# working.net
KiCad netlist of a schematic drawn in EAGLE
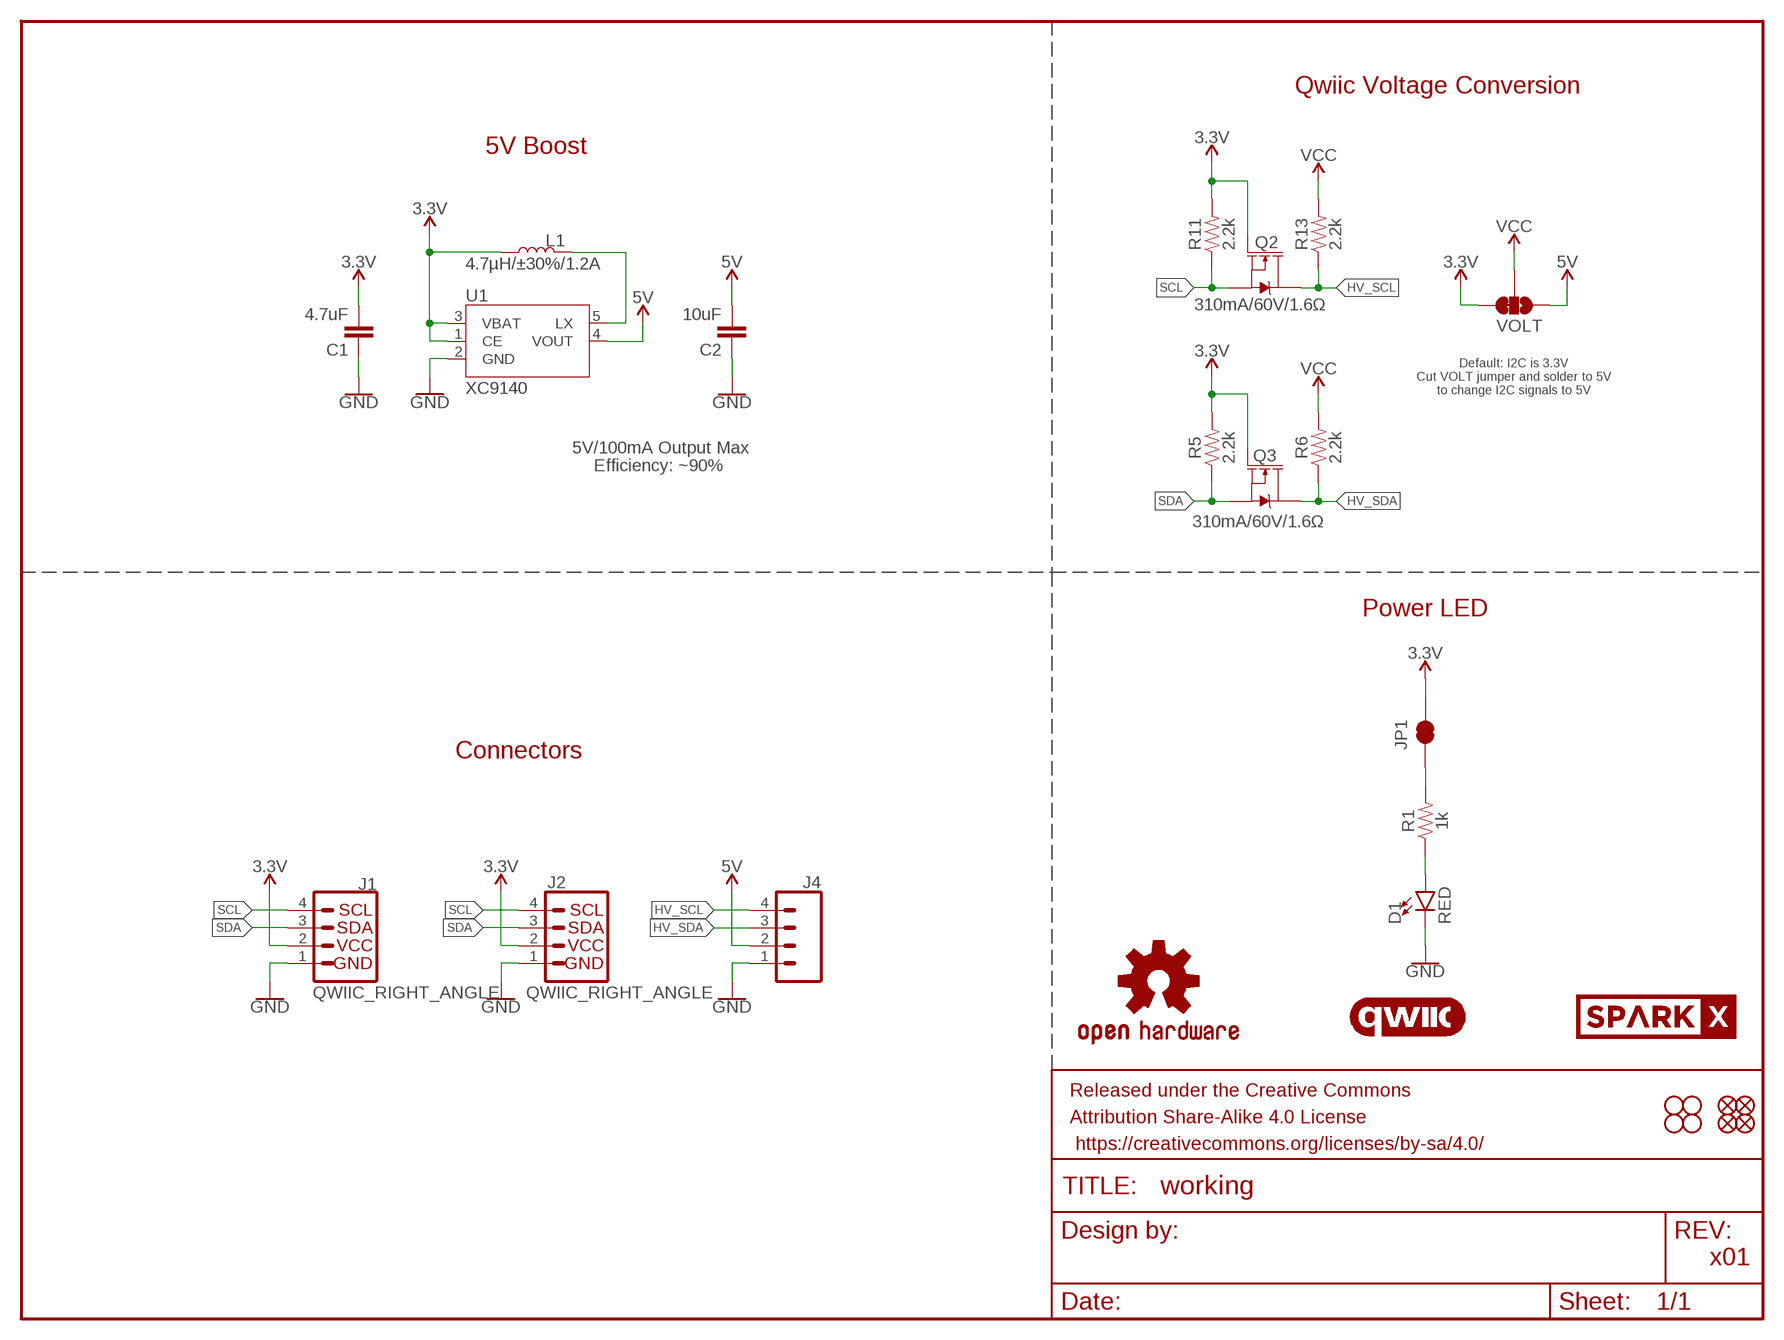
[diagram p0: schematic, sheet 1]

(export (version "E")
  (design (tool "Eeschema 10.0.6"))
  (components
    (comp (ref "C1")
      (value "4.7uF")
      (footprint "eagle-import:0603")
      (libsource (lib "eagle-import") (part "4.7UF-0603-6.3V-(10%)"))
    )
    (comp (ref "C2")
      (value "10uF")
      (footprint "eagle-import:0603")
      (libsource (lib "eagle-import") (part "10UF-0603-6.3V-20%"))
    )
    (comp (ref "D1")
      (value "RED")
      (footprint "eagle-import:LED-0603")
      (libsource (lib "eagle-import") (part "LED-RED0603"))
    )
    (comp (ref "FD1")
      (value "FIDUCIAL1X2")
      (footprint "eagle-import:FIDUCIAL-1X2")
      (libsource (lib "eagle-import") (part "FIDUCIAL1X2"))
    )
    (comp (ref "FD2")
      (value "FIDUCIAL1X2")
      (footprint "eagle-import:FIDUCIAL-1X2")
      (libsource (lib "eagle-import") (part "FIDUCIAL1X2"))
    )
    (comp (ref "FD3")
      (value "FIDUCIAL1X2")
      (footprint "eagle-import:FIDUCIAL-1X2")
      (libsource (lib "eagle-import") (part "FIDUCIAL1X2"))
    )
    (comp (ref "FD4")
      (value "FIDUCIAL1X2")
      (footprint "eagle-import:FIDUCIAL-1X2")
      (libsource (lib "eagle-import") (part "FIDUCIAL1X2"))
    )
    (comp (ref "FRAME1")
      (value "FRAME-LETTER")
      (footprint "eagle-import:CREATIVE_COMMONS")
      (libsource (lib "eagle-import") (part "FRAME-LETTER"))
    )
    (comp (ref "H1")
      (value "STAND-OFF")
      (footprint "eagle-import:STAND-OFF")
      (libsource (lib "eagle-import") (part "STAND-OFF"))
    )
    (comp (ref "H2")
      (value "STAND-OFF")
      (footprint "eagle-import:STAND-OFF")
      (libsource (lib "eagle-import") (part "STAND-OFF"))
    )
    (comp (ref "H3")
      (value "STAND-OFF")
      (footprint "eagle-import:STAND-OFF")
      (libsource (lib "eagle-import") (part "STAND-OFF"))
    )
    (comp (ref "H4")
      (value "STAND-OFF")
      (footprint "eagle-import:STAND-OFF")
      (libsource (lib "eagle-import") (part "STAND-OFF"))
    )
    (comp (ref "J1")
      (value "QWIIC_RIGHT_ANGLE")
      (footprint "eagle-import:JST04_1MM_RA")
      (libsource (lib "eagle-import") (part "QWIIC_CONNECTORJS-1MM"))
    )
    (comp (ref "J2")
      (value "QWIIC_RIGHT_ANGLE")
      (footprint "eagle-import:JST04_1MM_RA")
      (libsource (lib "eagle-import") (part "QWIIC_CONNECTORJS-1MM"))
    )
    (comp (ref "J4")
      (value "CONN_041X04_NO_SILK_NO_POP")
      (footprint "eagle-import:1X04_NO_SILK")
      (libsource (lib "eagle-import") (part "CONN_041X04_NO_SILK_NO_POP"))
    )
    (comp (ref "JP1")
      (value "JUMPER-SMT_2_NC_TRACE_SILK")
      (footprint "eagle-import:SMT-JUMPER_2_NC_TRACE_SILK")
      (libsource (lib "eagle-import") (part "JUMPER-SMT_2_NC_TRACE_SILK"))
    )
    (comp (ref "L1")
      (value "4.7µH/±30%/1.2A")
      (footprint "eagle-import:INDUCTOR_4.7UH")
      (libsource (lib "eagle-import") (part "INDUCTOR-CDRH-4.7UH"))
    )
    (comp (ref "LOGO1")
      (value "QWIIC_LOGO_CONNECTOR")
      (footprint "eagle-import:QWIIC_5.5MM")
      (libsource (lib "eagle-import") (part "QWIIC_LOGO_CONNECTOR"))
    )
    (comp (ref "LOGO2")
      (value "OSHW-LOGOMINI")
      (footprint "eagle-import:OSHW-LOGO-MINI")
      (libsource (lib "eagle-import") (part "OSHW-LOGOMINI"))
    )
    (comp (ref "Q2")
      (value "310mA/60V/1.6Ω")
      (footprint "eagle-import:SOT323")
      (libsource (lib "eagle-import") (part "MOSFET-NCH-2N7002PW"))
    )
    (comp (ref "Q3")
      (value "310mA/60V/1.6Ω")
      (footprint "eagle-import:SOT323")
      (libsource (lib "eagle-import") (part "MOSFET-NCH-2N7002PW"))
    )
    (comp (ref "R1")
      (value "1k")
      (footprint "eagle-import:0603")
      (libsource (lib "eagle-import") (part "1KOHM-0603-1/10W-1%"))
    )
    (comp (ref "R5")
      (value "2.2k")
      (footprint "eagle-import:0603")
      (libsource (lib "eagle-import") (part "2.2KOHM-0603-1/10W-1%"))
    )
    (comp (ref "R6")
      (value "2.2k")
      (footprint "eagle-import:0603")
      (libsource (lib "eagle-import") (part "2.2KOHM-0603-1/10W-1%"))
    )
    (comp (ref "R11")
      (value "2.2k")
      (footprint "eagle-import:0603")
      (libsource (lib "eagle-import") (part "2.2KOHM-0603-1/10W-1%"))
    )
    (comp (ref "R13")
      (value "2.2k")
      (footprint "eagle-import:0603")
      (libsource (lib "eagle-import") (part "2.2KOHM-0603-1/10W-1%"))
    )
    (comp (ref "U$8")
      (value "SPARKX-LOGO4")
      (footprint "eagle-import:SPARKX-MEDIUM")
      (libsource (lib "eagle-import") (part "SPARKX-LOGO4"))
    )
    (comp (ref "U1")
      (value "XC9140")
      (footprint "eagle-import:SOT23-5")
      (libsource (lib "eagle-import") (part "XC9140"))
    )
    (comp (ref "VOLT")
      (value "JUMPER-SMT_3_1-NC_TRACE_SILK")
      (footprint "eagle-import:SMT-JUMPER_3_1-NC_TRACE_SILK")
      (libsource (lib "eagle-import") (part "JUMPER-SMT_3_1-NC_TRACE_SILK"))
    )
  )
  (nets
    (net (code "1") (name "3.3V") (class "Default")
      (node (ref "C1") (pin "2") (pinfunction "2_2") (pintype "passive"))
      (node (ref "J1") (pin "2") (pinfunction "2_2") (pintype "power_in"))
      (node (ref "J2") (pin "2") (pinfunction "2_2") (pintype "power_in"))
      (node (ref "JP1") (pin "2") (pinfunction "2_2") (pintype "passive"))
      (node (ref "L1") (pin "P$2") (pinfunction "2_P$2") (pintype "passive"))
      (node (ref "Q2") (pin "1") (pinfunction "G_1") (pintype "bidirectional"))
      (node (ref "Q3") (pin "1") (pinfunction "G_1") (pintype "bidirectional"))
      (node (ref "R11") (pin "2") (pinfunction "2_2") (pintype "passive"))
      (node (ref "R5") (pin "2") (pinfunction "2_2") (pintype "passive"))
      (node (ref "U1") (pin "1") (pinfunction "CE_1") (pintype "input"))
      (node (ref "U1") (pin "3") (pinfunction "VBAT_3") (pintype "power_in"))
      (node (ref "VOLT") (pin "3") (pinfunction "3_3") (pintype "passive"))
    )
    (net (code "2") (name "5V") (class "Default")
      (node (ref "C2") (pin "2") (pinfunction "2_2") (pintype "passive"))
      (node (ref "J4") (pin "2") (pinfunction "2_2") (pintype "passive"))
      (node (ref "U1") (pin "4") (pinfunction "VOUT_4") (pintype "output"))
      (node (ref "VOLT") (pin "1") (pinfunction "1_1") (pintype "passive"))
    )
    (net (code "3") (name "GND") (class "Default")
      (node (ref "C1") (pin "1") (pinfunction "1_1") (pintype "passive"))
      (node (ref "C2") (pin "1") (pinfunction "1_1") (pintype "passive"))
      (node (ref "D1") (pin "C") (pinfunction "C_C") (pintype "passive"))
      (node (ref "J1") (pin "1") (pinfunction "1_1") (pintype "power_in"))
      (node (ref "J2") (pin "1") (pinfunction "1_1") (pintype "power_in"))
      (node (ref "J4") (pin "1") (pinfunction "1_1") (pintype "passive"))
      (node (ref "U1") (pin "2") (pinfunction "GND_2") (pintype "power_in"))
    )
    (net (code "4") (name "HV_SCL") (class "Default")
      (node (ref "J4") (pin "4") (pinfunction "4_4") (pintype "passive"))
      (node (ref "Q2") (pin "3") (pinfunction "D_3") (pintype "bidirectional"))
      (node (ref "R13") (pin "1") (pinfunction "1_1") (pintype "passive"))
    )
    (net (code "5") (name "HV_SDA") (class "Default")
      (node (ref "J4") (pin "3") (pinfunction "3_3") (pintype "passive"))
      (node (ref "Q3") (pin "3") (pinfunction "D_3") (pintype "bidirectional"))
      (node (ref "R6") (pin "1") (pinfunction "1_1") (pintype "passive"))
    )
    (net (code "6") (name "Net-(D1-PadA)") (class "Default")
      (node (ref "D1") (pin "A") (pinfunction "A_A") (pintype "passive"))
      (node (ref "R1") (pin "1") (pinfunction "1_1") (pintype "passive"))
    )
    (net (code "7") (name "Net-(JP1-Pad1)") (class "Default")
      (node (ref "JP1") (pin "1") (pinfunction "1_1") (pintype "passive"))
      (node (ref "R1") (pin "2") (pinfunction "2_2") (pintype "passive"))
    )
    (net (code "8") (name "Net-(L1-1)") (class "Default")
      (node (ref "L1") (pin "P$1") (pinfunction "1_P$1") (pintype "passive"))
      (node (ref "U1") (pin "5") (pinfunction "LX_5") (pintype "input"))
    )
    (net (code "9") (name "SCL") (class "Default")
      (node (ref "J1") (pin "4") (pinfunction "4_4") (pintype "passive"))
      (node (ref "J2") (pin "4") (pinfunction "4_4") (pintype "passive"))
      (node (ref "Q2") (pin "2") (pinfunction "S_2") (pintype "bidirectional"))
      (node (ref "R11") (pin "1") (pinfunction "1_1") (pintype "passive"))
    )
    (net (code "10") (name "SDA") (class "Default")
      (node (ref "J1") (pin "3") (pinfunction "3_3") (pintype "passive"))
      (node (ref "J2") (pin "3") (pinfunction "3_3") (pintype "passive"))
      (node (ref "Q3") (pin "2") (pinfunction "S_2") (pintype "bidirectional"))
      (node (ref "R5") (pin "1") (pinfunction "1_1") (pintype "passive"))
    )
    (net (code "11") (name "VCC") (class "Default")
      (node (ref "R13") (pin "2") (pinfunction "2_2") (pintype "passive"))
      (node (ref "R6") (pin "2") (pinfunction "2_2") (pintype "passive"))
      (node (ref "VOLT") (pin "2") (pinfunction "2_2") (pintype "passive"))
    )
  )
)
